# 1_Supply.net
KiCad netlist of a schematic drawn in Altium Designer
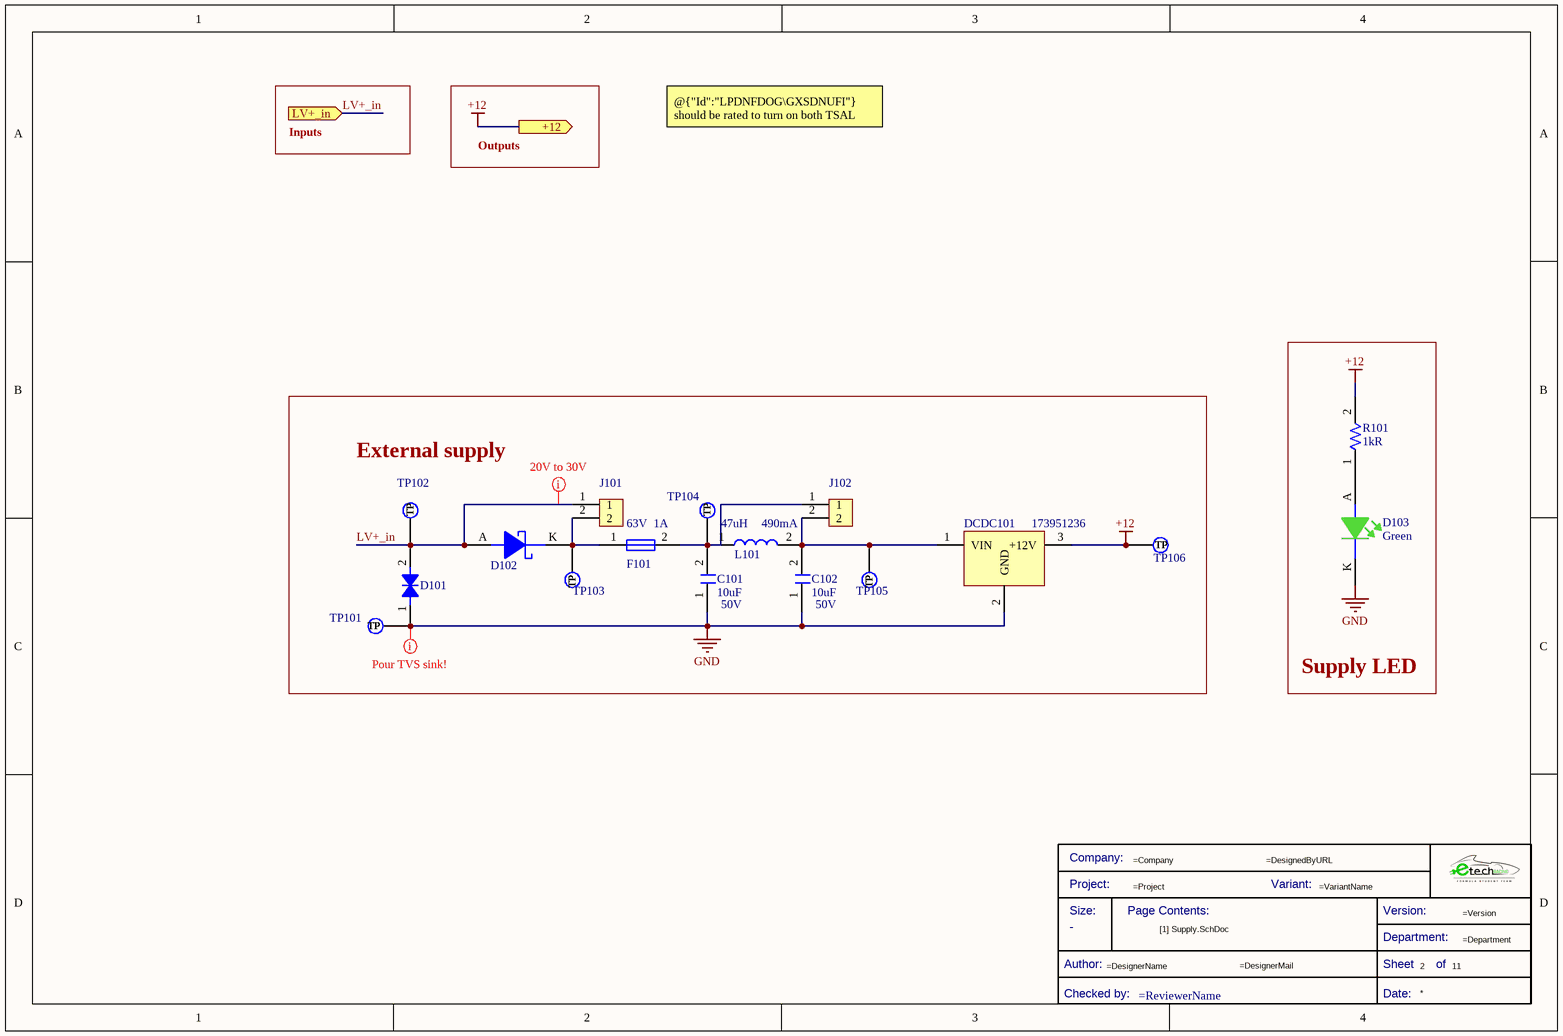
[diagram p0: [1] Supply.SchDoc]

(export (version "E")
  (design (tool "Eeschema 10.0.6"))
  (components
    (comp (ref "*")
      (value "Title Block_template")
      (description "Standard Title Block")
      (fields
        (field (name "SIZE") "-")
        (field (name ".CREATOR") "GP")
        (field (name ".PCBCHECK") "GP")
        (field (name ".SCHCHECK") "GP")
      )
      (libsource (lib "e-Tech_Racing") (part "Title Block_template"))
    )
    (comp (ref "C101")
      (value "GRJ32ER71H106KE11L")
      (footprint "C10u-50V-1210FNPMLCC-X7R")
      (description "Multilayer Ceramic Capacitors MLCC - SMD/SMT 1210 10uF 50volts X7R +/-10% Soft Term")
      (fields
        (field (name "MANUFACTURER") "Murata")
        (field (name "VOLTAGE RATING") "50V")
        (field (name "TOLERANCE") "10%")
        (field (name "CAPACITANCE") "10uF")
        (field (name ".CREATOR") "DR")
      )
      (libsource (lib "Passives") (part "C10u-50V-1210FNPMLCC-X7R"))
    )
    (comp (ref "C102")
      (value "GRJ32ER71H106KE11L")
      (footprint "C10u-50V-1210FNPMLCC-X7R")
      (description "Multilayer Ceramic Capacitors MLCC - SMD/SMT 1210 10uF 50volts X7R +/-10% Soft Term")
      (fields
        (field (name "MANUFACTURER") "Murata")
        (field (name "VOLTAGE RATING") "50V")
        (field (name "TOLERANCE") "10%")
        (field (name "CAPACITANCE") "10uF")
        (field (name ".CREATOR") "DR")
      )
      (libsource (lib "Passives") (part "C10u-50V-1210FNPMLCC-X7R"))
    )
    (comp (ref "D101")
      (value "824551301")
      (footprint "DTVS-DO-214AB")
      (description "TVS diode [Würth Elektronik] 824551301 TVS diode")
      (fields (field (name "MANUFACTURER") "Wurth Electronics") (field (name ".CREATOR") "DO"))
      (libsource (lib "Filter components") (part "DTVS-40V-DO-214AB"))
    )
    (comp (ref "D102")
      (value "MBR0530")
      (footprint "DSC-SOD123")
      (description "VR=30V IF=500mA 30pF P=410mW")
      (fields (field (name ".CREATOR") "GP"))
      (libsource (lib "Filter components") (part "DSC-0.5/30-SOD123"))
    )
    (comp (ref "D103")
      (value "150080VS75000")
      (footprint "LED_0805_WE")
      (description "Led, Green, 570 Nm, 2 V, 30 Ma, 40 Mcd Rohs Compliant: Yes")
      (fields (field (name "COLOR") "Green") (field (name ".CREATOR") "DR"))
      (libsource (lib "Semiconductor") (part "LEDVS-0805-40"))
    )
    (comp (ref "DCDC101")
      (value "173951236")
      (footprint "DCDC_Magi3c")
      (description "Fdsm Fixed Step Down Regulator M")
      (libsource (lib "Semiconductor") (part "DCDC-36V/12V-0.5A"))
    )
    (comp (ref "F101")
      (value "0437001.WRA")
      (footprint "Fuse_1206")
      (description "Fuse Chip Fast Acting 1A 63V SMD Solder Pad 1206 Ceramic T/R Automotive")
      (fields
        (field (name "MANUFACTURER") "Littelfuse")
        (field (name "CURRENT RATING") "1A")
        (field (name "VOLTAGE RATING (DC)") "63V")
        (field (name ".CREATOR") "DO")
      )
      (libsource (lib "Filter components") (part "Fuse_1A_63V_1206"))
    )
    (comp (ref "J101")
      (value "61300211121")
      (footprint "J_Pinheader_1x2")
      (description "CONN HEADER 2 POS 2.54")
      (fields (field (name "MANUFACTURER") "Molex") (field (name ".CREATOR") "GP"))
      (libsource (lib "Electromechanical") (part "J_Jumper"))
    )
    (comp (ref "J102")
      (value "61300211121")
      (footprint "J_Pinheader_1x2")
      (description "CONN HEADER 2 POS 2.54")
      (fields (field (name "MANUFACTURER") "Molex") (field (name ".CREATOR") "GP"))
      (libsource (lib "Electromechanical") (part "J_Jumper"))
    )
    (comp (ref "L101")
      (value "CDC5D23BNP-470KC")
      (footprint "L_47u-490mA_CF")
      (description "Inductor Power Unshielded Wirewound 47uH 10% 100KHz Ferrite 490mA 546mOhm DCR T/R")
      (fields
        (field (name "MANUFACTURER") "Sumida")
        (field (name "TOLERANCE") "10%")
        (field (name "CURRENT RATING") "490mA")
        (field (name "INDUCTANCE") "47uH")
        (field (name ".CREATOR") "GP")
      )
      (libsource (lib "Passives") (part "L_47u-490mA_CF"))
    )
    (comp (ref "R101")
      (value "CR0805-JW-102ELF")
      (footprint "R0805FTK")
      (description "Res Thick Film 0805 1K Ohm 5% 1/8W ±200ppm/°C Molded SMD SMD Paper Tape on Plastic Reel")
      (fields
        (field (name "TOLERANCE") "5%")
        (field (name "RESISTANCE") "1kR")
        (field (name ".CREATOR") "GP")
      )
      (libsource (lib "Passives") (part "R1k-0805FTK"))
    )
    (comp (ref "TP101")
      (value "TestPoint")
      (footprint "TestPoint")
      (description "Test Point 1x1 mm")
      (fields (field (name ".CREATOR") "GP") (field (name ".PCBCHECK") "GP") (field (name ".SCHCHECK") "GP"))
      (libsource (lib "e-Tech_Racing") (part "TestPoint"))
    )
    (comp (ref "TP102")
      (value "TestPoint")
      (footprint "TestPoint")
      (description "Test Point 1x1 mm")
      (fields (field (name ".CREATOR") "GP") (field (name ".PCBCHECK") "GP") (field (name ".SCHCHECK") "GP"))
      (libsource (lib "e-Tech_Racing") (part "TestPoint"))
    )
    (comp (ref "TP103")
      (value "TestPoint")
      (footprint "TestPoint")
      (description "Test Point 1x1 mm")
      (fields (field (name ".CREATOR") "GP") (field (name ".PCBCHECK") "GP") (field (name ".SCHCHECK") "GP"))
      (libsource (lib "e-Tech_Racing") (part "TestPoint"))
    )
    (comp (ref "TP104")
      (value "TestPoint")
      (footprint "TestPoint")
      (description "Test Point 1x1 mm")
      (fields (field (name ".CREATOR") "GP") (field (name ".PCBCHECK") "GP") (field (name ".SCHCHECK") "GP"))
      (libsource (lib "e-Tech_Racing") (part "TestPoint"))
    )
    (comp (ref "TP105")
      (value "TestPoint")
      (footprint "TestPoint")
      (description "Test Point 1x1 mm")
      (fields (field (name ".CREATOR") "GP") (field (name ".PCBCHECK") "GP") (field (name ".SCHCHECK") "GP"))
      (libsource (lib "e-Tech_Racing") (part "TestPoint"))
    )
    (comp (ref "TP106")
      (value "TestPoint")
      (footprint "TestPoint")
      (description "Test Point 1x1 mm")
      (fields (field (name ".CREATOR") "GP") (field (name ".PCBCHECK") "GP") (field (name ".SCHCHECK") "GP"))
      (libsource (lib "e-Tech_Racing") (part "TestPoint"))
    )
  )
  (nets
    (net (code "1") (name "+12") (class "Default")
      (node (ref "DCDC101") (pin "3") (pinfunction "+12V_3") (pintype "passive"))
      (node (ref "R101") (pin "2") (pinfunction "2_2") (pintype "passive"))
      (node (ref "TP106") (pin "1") (pinfunction "TP_1") (pintype "passive"))
    )
    (net (code "2") (name "/LV+_in") (class "Default")
      (node (ref "D101") (pin "2") (pinfunction "2_2") (pintype "passive"))
      (node (ref "D102") (pin "A") (pinfunction "A_A") (pintype "passive"))
      (node (ref "J101") (pin "1") (pinfunction "1_1") (pintype "passive"))
      (node (ref "TP102") (pin "1") (pinfunction "TP_1") (pintype "passive"))
    )
    (net (code "3") (name "GND") (class "Default")
      (node (ref "C101") (pin "1") (pinfunction "1_1") (pintype "passive"))
      (node (ref "C102") (pin "1") (pinfunction "1_1") (pintype "passive"))
      (node (ref "D101") (pin "1") (pinfunction "1_1") (pintype "passive"))
      (node (ref "D103") (pin "K") (pinfunction "K_K") (pintype "passive"))
      (node (ref "DCDC101") (pin "2") (pinfunction "GND_2") (pintype "passive"))
      (node (ref "TP101") (pin "1") (pinfunction "TP_1") (pintype "passive"))
    )
    (net (code "4") (name "Net-(D103-PadA)") (class "Default")
      (node (ref "D103") (pin "A") (pinfunction "A_A") (pintype "passive"))
      (node (ref "R101") (pin "1") (pinfunction "1_1") (pintype "passive"))
    )
    (net (code "5") (name "Net-(DCDC101-VIN)") (class "Default")
      (node (ref "C102") (pin "2") (pinfunction "2_2") (pintype "passive"))
      (node (ref "DCDC101") (pin "1") (pinfunction "VIN_1") (pintype "passive"))
      (node (ref "J102") (pin "2") (pinfunction "2_2") (pintype "passive"))
      (node (ref "L101") (pin "2") (pinfunction "2_2") (pintype "passive"))
      (node (ref "TP105") (pin "1") (pinfunction "TP_1") (pintype "passive"))
    )
    (net (code "6") (name "Net-(TP103-TP)") (class "Default")
      (node (ref "D102") (pin "K") (pinfunction "K_K") (pintype "passive"))
      (node (ref "F101") (pin "1") (pinfunction "1_1") (pintype "passive"))
      (node (ref "J101") (pin "2") (pinfunction "2_2") (pintype "passive"))
      (node (ref "TP103") (pin "1") (pinfunction "TP_1") (pintype "passive"))
    )
    (net (code "7") (name "Net-(TP104-TP)") (class "Default")
      (node (ref "C101") (pin "2") (pinfunction "2_2") (pintype "passive"))
      (node (ref "F101") (pin "2") (pinfunction "2_2") (pintype "passive"))
      (node (ref "J102") (pin "1") (pinfunction "1_1") (pintype "passive"))
      (node (ref "L101") (pin "1") (pinfunction "1_1") (pintype "passive"))
      (node (ref "TP104") (pin "1") (pinfunction "TP_1") (pintype "passive"))
    )
  )
)
